# PIR_Sensor_driver_v4.net
KiCad netlist of a schematic drawn in Altium Designer
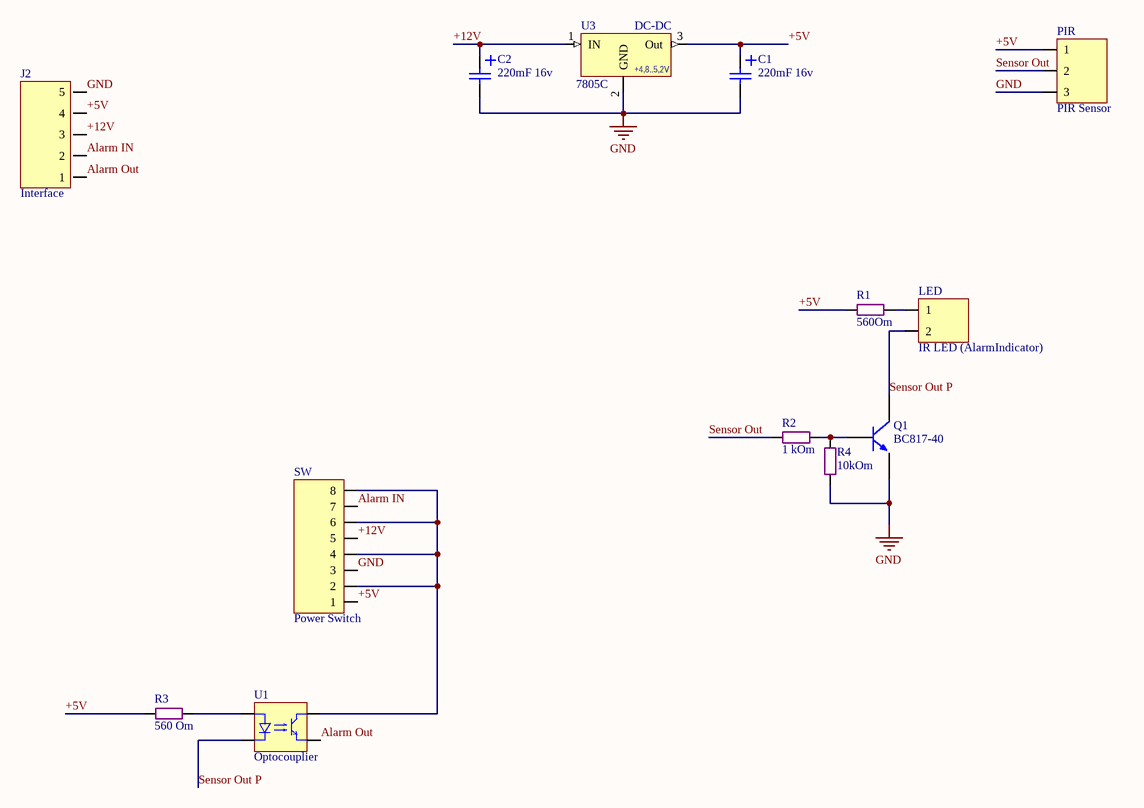
[diagram p0: PIR Sensor driver v4.SchDoc]

(export (version "E")
  (design (tool "Eeschema 10.0.6"))
  (components
    (comp (ref "C1")
      (value "220mF 16v")
      (footprint "Capacitor:Cap E p4mm D6.5xH11")
      (description "Capacitor")
      (libsource (lib "Capacitor") (part "Cap E 220mF x 16V"))
    )
    (comp (ref "C2")
      (value "220mF 16v")
      (footprint "Capacitor:Cap E p2mm D6.5xH11")
      (description "Capacitor")
      (libsource (lib "Capacitor") (part "Cap E 220mF x 16V"))
    )
    (comp (ref "J2")
      (value "Interface")
      (footprint "Connector:Line 2.54 x 5 - (D2mm)")
      (description "Vert, Sgl line, Male")
      (libsource (lib "Connector") (part "PLS-5"))
    )
    (comp (ref "LED")
      (value "IR LED (AlarmIndicator)")
      (footprint "Connector:Line 2.54 x 2")
      (description "Vert, Sgl line, Male")
      (libsource (lib "Connector") (part "PLS-2"))
    )
    (comp (ref "PIR")
      (value "PIR Sensor")
      (footprint "Connector:Line 2.54 X 3")
      (description "Vert, Sgl line, Male")
      (libsource (lib "Connector") (part "PLS-3"))
    )
    (comp (ref "Q1")
      (value "BC817-40")
      (footprint "GeneralCases:SOT-23")
      (description "NPN 45 V, 500 mA NPN general-purpose transistor")
      (libsource (lib "Transistor") (part "BC817-40"))
    )
    (comp (ref "R1")
      (value "560Om")
      (footprint "PassiveComponents:SMD 0805 (2012) Long")
      (libsource (lib "PassiveComponents") (part "Res All Types"))
    )
    (comp (ref "R2")
      (value "1 kOm")
      (footprint "SMD 0805 (2012)")
      (libsource (lib "PassiveComponents") (part "Res SMD 0805"))
    )
    (comp (ref "R3")
      (value "560 Om")
      (footprint "SMD 0805 (2012)")
      (libsource (lib "PassiveComponents") (part "Res SMD 0805"))
    )
    (comp (ref "R4")
      (value "10kOm")
      (footprint "PassiveComponents:SMD 0805 (2012)")
      (libsource (lib "PassiveComponents") (part "Res All Types"))
    )
    (comp (ref "SW")
      (value "Power Switch")
      (footprint "Connector:Line 2.54 X 8D (2 x 4)")
      (description "Vert, Sgl line, Male")
      (libsource (lib "Connector") (part "PLD-8 (2 x 4)"))
    )
    (comp (ref "U1")
      (value "Optocouplier")
      (footprint "GeneralCases:DIP-4")
      (libsource (lib "Transistor") (part "Optocouplier LTV 817B"))
    )
    (comp (ref "U3")
      (value "7805C")
      (footprint "GeneralCases:D-PAK")
      (description "Voltage Regulator")
      (fields (field (name "MANUFACTURER") "Интеграл") (field (name "V OUT") "+4,8..5,2V"))
      (libsource (lib "PowerAdjusment") (part "7805C"))
    )
  )
  (nets
    (net (code "1") (name "/+5V") (class "Default")
      (node (ref "C1") (pin "1") (pinfunction "1_1") (pintype "passive"))
      (node (ref "J2") (pin "4") (pinfunction "4_4") (pintype "passive"))
      (node (ref "PIR") (pin "1") (pinfunction "1_1") (pintype "passive"))
      (node (ref "R1") (pin "1") (pinfunction "1_1") (pintype "passive"))
      (node (ref "R3") (pin "1") (pinfunction "1_1") (pintype "passive"))
      (node (ref "SW") (pin "1") (pinfunction "1_1") (pintype "passive"))
      (node (ref "U3") (pin "3") (pinfunction "Out_3") (pintype "output"))
    )
    (net (code "2") (name "/+12V") (class "Default")
      (node (ref "C2") (pin "1") (pinfunction "1_1") (pintype "passive"))
      (node (ref "J2") (pin "3") (pinfunction "3_3") (pintype "passive"))
      (node (ref "SW") (pin "5") (pinfunction "5_5") (pintype "passive"))
      (node (ref "U3") (pin "1") (pinfunction "IN_1") (pintype "input"))
    )
    (net (code "3") (name "/Alarm IN") (class "Default")
      (node (ref "J2") (pin "2") (pinfunction "2_2") (pintype "passive"))
      (node (ref "SW") (pin "7") (pinfunction "7_7") (pintype "passive"))
    )
    (net (code "4") (name "/Alarm Out") (class "Default")
      (node (ref "J2") (pin "1") (pinfunction "1_1") (pintype "passive"))
      (node (ref "U1") (pin "4") (pinfunction "4_4") (pintype "passive"))
    )
    (net (code "5") (name "/Sensor Out") (class "Default")
      (node (ref "PIR") (pin "2") (pinfunction "2_2") (pintype "passive"))
      (node (ref "R2") (pin "1") (pinfunction "1_1") (pintype "passive"))
    )
    (net (code "6") (name "/Sensor Out P") (class "Default")
      (node (ref "LED") (pin "2") (pinfunction "2_2") (pintype "passive"))
      (node (ref "Q1") (pin "3") (pinfunction "C_3") (pintype "passive"))
      (node (ref "U1") (pin "2") (pinfunction "2_2") (pintype "passive"))
    )
    (net (code "7") (name "GND") (class "Default")
      (node (ref "C1") (pin "2") (pinfunction "2_2") (pintype "passive"))
      (node (ref "C2") (pin "2") (pinfunction "2_2") (pintype "passive"))
      (node (ref "J2") (pin "5") (pinfunction "5_5") (pintype "passive"))
      (node (ref "PIR") (pin "3") (pinfunction "3_3") (pintype "passive"))
      (node (ref "Q1") (pin "2") (pinfunction "E_2") (pintype "passive"))
      (node (ref "R4") (pin "1") (pinfunction "1_1") (pintype "passive"))
      (node (ref "SW") (pin "3") (pinfunction "3_3") (pintype "passive"))
      (node (ref "U3") (pin "2") (pinfunction "GND_2") (pintype "passive"))
    )
    (net (code "8") (name "Net-(LED-Pad1)") (class "Default")
      (node (ref "LED") (pin "1") (pinfunction "1_1") (pintype "passive"))
      (node (ref "R1") (pin "2") (pinfunction "2_2") (pintype "passive"))
    )
    (net (code "9") (name "Net-(Q1-B)") (class "Default")
      (node (ref "Q1") (pin "1") (pinfunction "B_1") (pintype "passive"))
      (node (ref "R2") (pin "2") (pinfunction "2_2") (pintype "passive"))
      (node (ref "R4") (pin "2") (pinfunction "2_2") (pintype "passive"))
    )
    (net (code "10") (name "Net-(R3-Pad2)") (class "Default")
      (node (ref "R3") (pin "2") (pinfunction "2_2") (pintype "passive"))
      (node (ref "U1") (pin "1") (pinfunction "1_1") (pintype "passive"))
    )
    (net (code "11") (name "Net-(SW-Pad2)") (class "Default")
      (node (ref "SW") (pin "2") (pinfunction "2_2") (pintype "passive"))
      (node (ref "SW") (pin "4") (pinfunction "4_4") (pintype "passive"))
      (node (ref "SW") (pin "6") (pinfunction "6_6") (pintype "passive"))
      (node (ref "SW") (pin "8") (pinfunction "8_8") (pintype "passive"))
      (node (ref "U1") (pin "3") (pinfunction "3_3") (pintype "passive"))
    )
  )
)
